# Priority_Encoder.net
KiCad netlist of a schematic drawn in Altium Designer
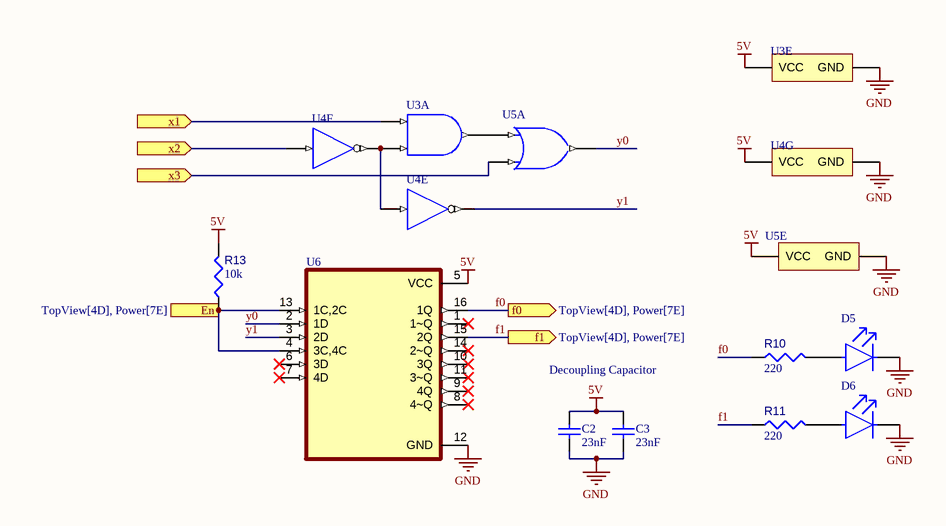
[diagram p0: Priority_Encoder.SchDoc]

(export (version "E")
  (design (tool "Eeschema 10.0.6"))
  (components
    (comp (ref "C2")
      (value "23nF")
      (footprint "KEMT-C315-THT-2")
      (description "Capacitor, Ceramic, 0.01 uF, +/- 10%, 100 V, X7R, -55 to 125 degC, 2-Pin THD, RoHS, Bulk")
      (libsource (lib "Altium Content Vault") (part "CAP-NP-2"))
    )
    (comp (ref "C3")
      (value "23nF")
      (footprint "KEMT-C315-THT-2")
      (description "Capacitor, Ceramic, 0.01 uF, +/- 10%, 100 V, X7R, -55 to 125 degC, 2-Pin THD, RoHS, Bulk")
      (libsource (lib "Altium Content Vault") (part "CAP-NP-2"))
    )
    (comp (ref "D5")
      (value "LTL2P3KGKNN")
      (footprint "FP-LTL2P3KGKNN-MFG")
      (description "LED GREEN CLEAR T-1 3/4 T/H")
      (fields
        (field (name "MANUFACTURER") "Lite-On")
        (field (name "OCTOPART") "https://octopart.com/ltl2p3kgknn-lite-on-550036")
      )
      (libsource (lib "Altium Content Vault") (part "8706943c75ba83719d021d2fdc84c58"))
    )
    (comp (ref "D6")
      (value "LTL2P3KGKNN")
      (footprint "FP-LTL2P3KGKNN-MFG")
      (description "LED GREEN CLEAR T-1 3/4 T/H")
      (fields
        (field (name "MANUFACTURER") "Lite-On")
        (field (name "OCTOPART") "https://octopart.com/ltl2p3kgknn-lite-on-550036")
      )
      (libsource (lib "Altium Content Vault") (part "8706943c75ba83719d021d2fdc84c58"))
    )
    (comp (ref "R10")
      (value "220")
      (footprint "RESA60-630X240")
      (description "Axial Resistor, 100 Ohm, +/- 1%, 0.25 W, -55 to 155 degC, 2-Pin THD, RoHS, Bulk")
      (fields (field (name "MANUFACTURER") "Yageo") (field (name "TOLERANCE") "1%"))
      (libsource (lib "Brandon Ramos") (part "RES-2"))
    )
    (comp (ref "R11")
      (value "220")
      (footprint "RESA60-630X240")
      (description "Axial Resistor, 100 Ohm, +/- 1%, 0.25 W, -55 to 155 degC, 2-Pin THD, RoHS, Bulk")
      (fields (field (name "MANUFACTURER") "Yageo") (field (name "TOLERANCE") "1%"))
      (libsource (lib "Brandon Ramos") (part "RES-2"))
    )
    (comp (ref "R13")
      (value "10k")
      (footprint "RESA60-630X240")
      (description "Axial Resistor, 100 Ohm, +/- 1%, 0.25 W, -55 to 155 degC, 2-Pin THD, RoHS, Bulk")
      (fields (field (name "MANUFACTURER") "Yageo") (field (name "TOLERANCE") "1%"))
      (libsource (lib "Brandon Ramos") (part "RES-2"))
    )
    (comp (ref "U3")
      (value "SN74LS08N")
      (footprint "N0014A")
      (description "Quadruple 2-Input Positive-AND Gates, N0014A, TUBE")
      (fields
        (field (name "MANUFACTURER") "Texas Instruments")
        (field (name "GENERIC PART NUMBER") "SN74LS08")
      )
      (libsource (lib "Altium Content Vault") (part "TI-AND-4-2IN-14"))
    )
    (comp (ref "U4")
      (value "SN74LS04N")
      (footprint "N0014A")
      (description "Hex inverters, N0014A, TUBE")
      (fields
        (field (name "MANUFACTURER") "Texas Instruments")
        (field (name "GENERIC PART NUMBER") "SN74LS04")
      )
      (libsource (lib "") (part "TI-CD_SNX4XXXXXX4X_19A-14_1"))
    )
    (comp (ref "U5")
      (value "SN74LS32N")
      (footprint "N0014A")
      (description "Quad 2-input positive-OR gates, N0014A, TUBE")
      (fields
        (field (name "GENERIC PART NUMBER") "SN74LS32")
        (field (name "MANUFACTURER") "Texas Instruments")
      )
      (libsource (lib "Altium Content Vault") (part "TI-OR-4-2IN-14"))
    )
    (comp (ref "U6")
      (value "SN74LS75N")
      (footprint "SN74LS75N:DIP794W45P254L1969H508Q16")
      (description "Quad bistable latches")
      (fields (field (name "MF") "Texas Instruments"))
      (libsource (lib "SN74LS75N") (part "SN74LS75N"))
    )
  )
  (nets
    (net (code "1") (name "/En") (class "Default")
      (node (ref "R13") (pin "1") (pinfunction "1_1") (pintype "passive"))
      (node (ref "U6") (pin "13") (pinfunction "1C,2C_13") (pintype "input"))
      (node (ref "U6") (pin "4") (pinfunction "3C,4C_4") (pintype "input"))
    )
    (net (code "2") (name "/f0") (class "Default")
      (node (ref "R10") (pin "1") (pinfunction "1_1") (pintype "passive"))
      (node (ref "U6") (pin "16") (pinfunction "1Q_16") (pintype "output"))
    )
    (net (code "3") (name "/f1") (class "Default")
      (node (ref "R11") (pin "1") (pinfunction "1_1") (pintype "passive"))
      (node (ref "U6") (pin "15") (pinfunction "2Q_15") (pintype "output"))
    )
    (net (code "4") (name "/x1") (class "Default")
      (node (ref "U3") (pin "1") (pinfunction "1A_1") (pintype "input"))
    )
    (net (code "5") (name "/x2") (class "Default")
      (node (ref "U4") (pin "13") (pinfunction "6A_13") (pintype "input"))
    )
    (net (code "6") (name "/x3") (class "Default")
      (node (ref "U5") (pin "2") (pinfunction "1B_2") (pintype "input"))
    )
    (net (code "7") (name "/y0") (class "Default")
      (node (ref "U5") (pin "3") (pinfunction "1Y_3") (pintype "output"))
      (node (ref "U6") (pin "2") (pinfunction "1D_2") (pintype "input"))
    )
    (net (code "8") (name "/y1") (class "Default")
      (node (ref "U4") (pin "10") (pinfunction "~{5Y}_10") (pintype "output"))
      (node (ref "U6") (pin "3") (pinfunction "2D_3") (pintype "input"))
    )
    (net (code "9") (name "5V") (class "Default")
      (node (ref "C2") (pin "2") (pinfunction "2_2") (pintype "passive"))
      (node (ref "C3") (pin "2") (pinfunction "2_2") (pintype "passive"))
      (node (ref "R13") (pin "2") (pinfunction "2_2") (pintype "passive"))
      (node (ref "U3") (pin "14") (pinfunction "VCC_14") (pintype "power_in"))
      (node (ref "U4") (pin "14") (pinfunction "VCC_14") (pintype "power_in"))
      (node (ref "U5") (pin "14") (pinfunction "VCC_14") (pintype "power_in"))
      (node (ref "U6") (pin "5") (pinfunction "VCC_5") (pintype "power_in"))
    )
    (net (code "10") (name "GND") (class "Default")
      (node (ref "C2") (pin "1") (pinfunction "1_1") (pintype "passive"))
      (node (ref "C3") (pin "1") (pinfunction "1_1") (pintype "passive"))
      (node (ref "D5") (pin "1") (pinfunction "C_1") (pintype "passive"))
      (node (ref "D6") (pin "1") (pinfunction "C_1") (pintype "passive"))
      (node (ref "U3") (pin "7") (pinfunction "GND_7") (pintype "power_in"))
      (node (ref "U4") (pin "7") (pinfunction "GND_7") (pintype "power_in"))
      (node (ref "U5") (pin "7") (pinfunction "GND_7") (pintype "power_in"))
      (node (ref "U6") (pin "12") (pinfunction "GND_12") (pintype "power_in"))
    )
    (net (code "11") (name "Net-(D5-A)") (class "Default")
      (node (ref "D5") (pin "2") (pinfunction "A_2") (pintype "passive"))
      (node (ref "R10") (pin "2") (pinfunction "2_2") (pintype "passive"))
    )
    (net (code "12") (name "Net-(D6-A)") (class "Default")
      (node (ref "D6") (pin "2") (pinfunction "A_2") (pintype "passive"))
      (node (ref "R11") (pin "2") (pinfunction "2_2") (pintype "passive"))
    )
    (net (code "13") (name "Net-(U3A-1B)") (class "Default")
      (node (ref "U3") (pin "2") (pinfunction "1B_2") (pintype "input"))
      (node (ref "U4") (pin "11") (pinfunction "5A_11") (pintype "input"))
      (node (ref "U4") (pin "12") (pinfunction "~{6Y}_12") (pintype "output"))
    )
    (net (code "14") (name "Net-(U3A-1Y)") (class "Default")
      (node (ref "U3") (pin "3") (pinfunction "1Y_3") (pintype "output"))
      (node (ref "U5") (pin "1") (pinfunction "1A_1") (pintype "input"))
    )
    (net (code "15") (name "unconnected-(U6-1~Q-Pad1)") (class "Default")
      (node (ref "U6") (pin "1") (pinfunction "1~Q_1") (pintype "output+no_connect"))
    )
    (net (code "16") (name "unconnected-(U6-2~Q-Pad14)") (class "Default")
      (node (ref "U6") (pin "14") (pinfunction "2~Q_14") (pintype "output+no_connect"))
    )
    (net (code "17") (name "unconnected-(U6-3D-Pad6)") (class "Default")
      (node (ref "U6") (pin "6") (pinfunction "3D_6") (pintype "input+no_connect"))
    )
    (net (code "18") (name "unconnected-(U6-3Q-Pad10)") (class "Default")
      (node (ref "U6") (pin "10") (pinfunction "3Q_10") (pintype "output+no_connect"))
    )
    (net (code "19") (name "unconnected-(U6-3~Q-Pad11)") (class "Default")
      (node (ref "U6") (pin "11") (pinfunction "3~Q_11") (pintype "output+no_connect"))
    )
    (net (code "20") (name "unconnected-(U6-4D-Pad7)") (class "Default")
      (node (ref "U6") (pin "7") (pinfunction "4D_7") (pintype "input+no_connect"))
    )
    (net (code "21") (name "unconnected-(U6-4Q-Pad9)") (class "Default")
      (node (ref "U6") (pin "9") (pinfunction "4Q_9") (pintype "output+no_connect"))
    )
    (net (code "22") (name "unconnected-(U6-4~Q-Pad8)") (class "Default")
      (node (ref "U6") (pin "8") (pinfunction "4~Q_8") (pintype "output+no_connect"))
    )
  )
)
